# Pyr0-Piezo_Direct-Extruder-FFC-Breakout_.net
KiCad netlist of a schematic drawn in EAGLE
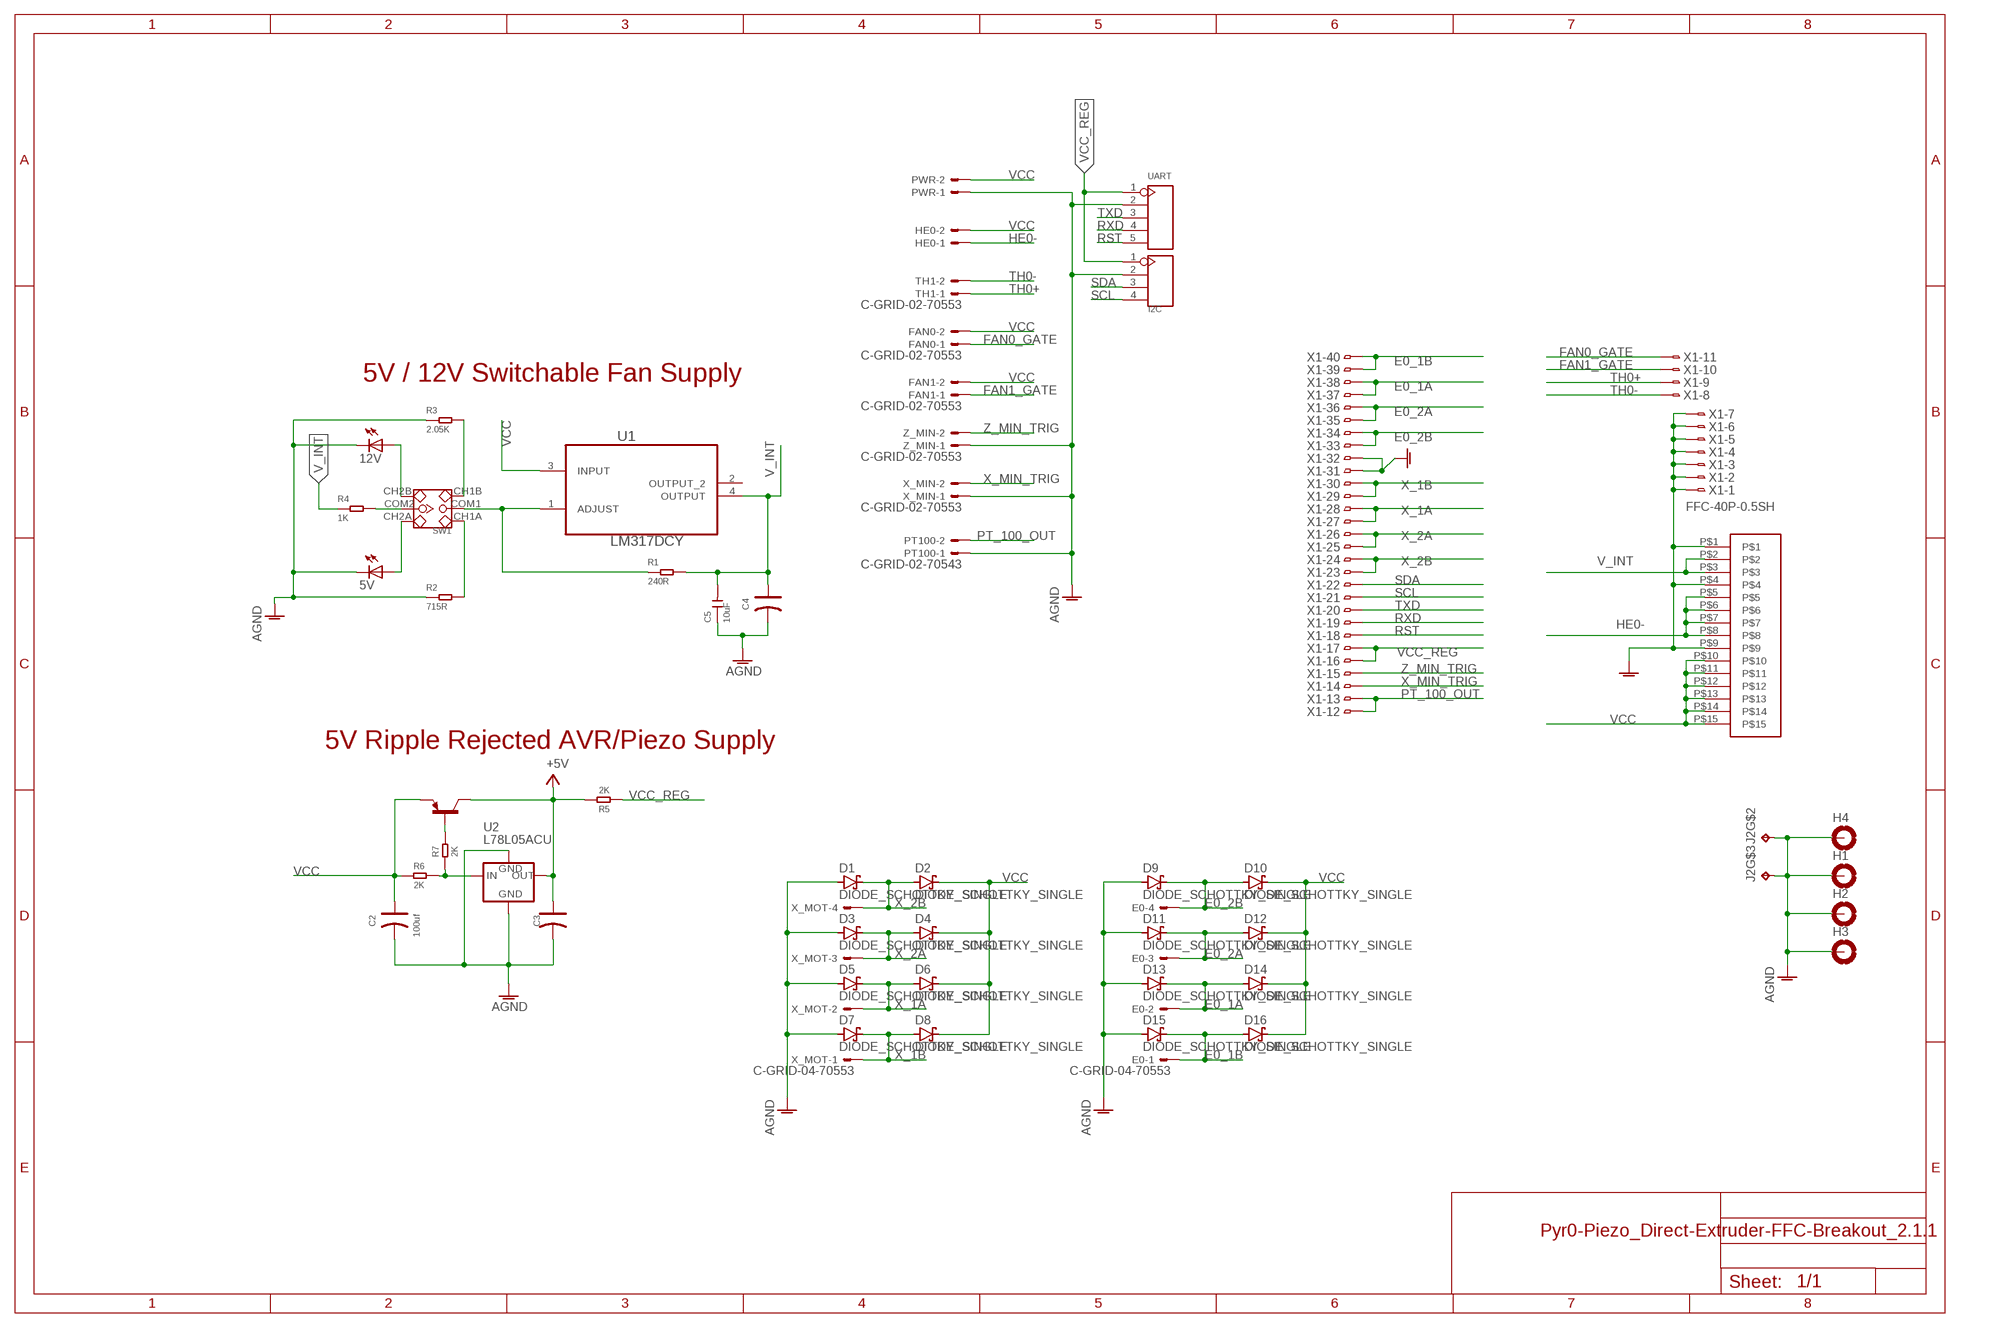
[diagram p0: schematic, sheet 1]

(export (version "E")
  (design (tool "Eeschema 10.0.6"))
  (components
    (comp (ref "5V")
      (value "LEDCHIP-LED0805")
      (footprint "eagle-import:CHIP-LED0805")
      (libsource (lib "eagle-import") (part "LEDCHIP-LED0805"))
    )
    (comp (ref "12V")
      (value "LEDCHIP-LED0805")
      (footprint "eagle-import:CHIP-LED0805")
      (libsource (lib "eagle-import") (part "LEDCHIP-LED0805"))
    )
    (comp (ref "C2")
      (value "100uf")
      (footprint "eagle-import:ALU-C-D5.3MM_LEFT")
      (fields (field (name "MPN") "KS 100uF/16V"))
      (libsource (lib "eagle-import") (part "DIP-ALUMINUM-100UF-16V(D5-H7MM)LEFT"))
    )
    (comp (ref "C3")
      (value "100uf")
      (footprint "eagle-import:ALU-C-D5.3MM_RIGHT")
      (libsource (lib "eagle-import") (part "DIP-ALUMINUM-100UF-16V(D5-H7MM)RIGHT"))
    )
    (comp (ref "C4")
      (value "100uf")
      (footprint "eagle-import:ALU-C-D5.3MM_RIGHT")
      (libsource (lib "eagle-import") (part "DIP-ALUMINUM-100UF-16V(D5-H7MM)RIGHT"))
    )
    (comp (ref "C5")
      (value "10uF")
      (footprint "eagle-import:CAPC2012X130")
      (libsource (lib "eagle-import") (part "SEEED-CAPACITOR_CERAMIC-10UF-25V-10%-X5R(0805)CAP_0805-3D"))
    )
    (comp (ref "D1")
      (value "DIODE_SCHOTTKY_SINGLE")
      (footprint "eagle-import:DO-214AC")
      (libsource (lib "eagle-import") (part "DIODE_SCHOTTKY_SINGLE"))
    )
    (comp (ref "D2")
      (value "DIODE_SCHOTTKY_SINGLE")
      (footprint "eagle-import:DO-214AC")
      (libsource (lib "eagle-import") (part "DIODE_SCHOTTKY_SINGLE"))
    )
    (comp (ref "D3")
      (value "DIODE_SCHOTTKY_SINGLE")
      (footprint "eagle-import:DO-214AC")
      (libsource (lib "eagle-import") (part "DIODE_SCHOTTKY_SINGLE"))
    )
    (comp (ref "D4")
      (value "DIODE_SCHOTTKY_SINGLE")
      (footprint "eagle-import:DO-214AC")
      (libsource (lib "eagle-import") (part "DIODE_SCHOTTKY_SINGLE"))
    )
    (comp (ref "D5")
      (value "DIODE_SCHOTTKY_SINGLE")
      (footprint "eagle-import:DO-214AC")
      (libsource (lib "eagle-import") (part "DIODE_SCHOTTKY_SINGLE"))
    )
    (comp (ref "D6")
      (value "DIODE_SCHOTTKY_SINGLE")
      (footprint "eagle-import:DO-214AC")
      (libsource (lib "eagle-import") (part "DIODE_SCHOTTKY_SINGLE"))
    )
    (comp (ref "D7")
      (value "DIODE_SCHOTTKY_SINGLE")
      (footprint "eagle-import:DO-214AC")
      (libsource (lib "eagle-import") (part "DIODE_SCHOTTKY_SINGLE"))
    )
    (comp (ref "D8")
      (value "DIODE_SCHOTTKY_SINGLE")
      (footprint "eagle-import:DO-214AC")
      (libsource (lib "eagle-import") (part "DIODE_SCHOTTKY_SINGLE"))
    )
    (comp (ref "D9")
      (value "DIODE_SCHOTTKY_SINGLE")
      (footprint "eagle-import:DO-214AC")
      (libsource (lib "eagle-import") (part "DIODE_SCHOTTKY_SINGLE"))
    )
    (comp (ref "D10")
      (value "DIODE_SCHOTTKY_SINGLE")
      (footprint "eagle-import:DO-214AC")
      (libsource (lib "eagle-import") (part "DIODE_SCHOTTKY_SINGLE"))
    )
    (comp (ref "D11")
      (value "DIODE_SCHOTTKY_SINGLE")
      (footprint "eagle-import:DO-214AC")
      (libsource (lib "eagle-import") (part "DIODE_SCHOTTKY_SINGLE"))
    )
    (comp (ref "D12")
      (value "DIODE_SCHOTTKY_SINGLE")
      (footprint "eagle-import:DO-214AC")
      (libsource (lib "eagle-import") (part "DIODE_SCHOTTKY_SINGLE"))
    )
    (comp (ref "D13")
      (value "DIODE_SCHOTTKY_SINGLE")
      (footprint "eagle-import:DO-214AC")
      (libsource (lib "eagle-import") (part "DIODE_SCHOTTKY_SINGLE"))
    )
    (comp (ref "D14")
      (value "DIODE_SCHOTTKY_SINGLE")
      (footprint "eagle-import:DO-214AC")
      (libsource (lib "eagle-import") (part "DIODE_SCHOTTKY_SINGLE"))
    )
    (comp (ref "D15")
      (value "DIODE_SCHOTTKY_SINGLE")
      (footprint "eagle-import:DO-214AC")
      (libsource (lib "eagle-import") (part "DIODE_SCHOTTKY_SINGLE"))
    )
    (comp (ref "D16")
      (value "DIODE_SCHOTTKY_SINGLE")
      (footprint "eagle-import:DO-214AC")
      (libsource (lib "eagle-import") (part "DIODE_SCHOTTKY_SINGLE"))
    )
    (comp (ref "E0")
      (value "C-GRID-04-70553")
      (footprint "eagle-import:70553-04")
      (fields (field (name "MF") "MOLEX"))
      (libsource (lib "eagle-import") (part "C-GRID-04-70553"))
    )
    (comp (ref "FAN0")
      (value "C-GRID-02-70553")
      (footprint "eagle-import:70553-02")
      (fields (field (name "MF") "MOLEX"))
      (libsource (lib "eagle-import") (part "C-GRID-02-70553"))
    )
    (comp (ref "FAN1")
      (value "C-GRID-02-70553")
      (footprint "eagle-import:70553-02")
      (fields (field (name "MF") "MOLEX"))
      (libsource (lib "eagle-import") (part "C-GRID-02-70553"))
    )
    (comp (ref "H1")
      (value "HOLES_MOUNT-PAD-ROUND3.2")
      (footprint "eagle-import:HOLES_3,2-PAD")
      (libsource (lib "eagle-import") (part "HOLES_MOUNT-PAD-ROUND3.2"))
    )
    (comp (ref "H2")
      (value "HOLES_MOUNT-PAD-ROUND3.2")
      (footprint "eagle-import:HOLES_3,2-PAD")
      (libsource (lib "eagle-import") (part "HOLES_MOUNT-PAD-ROUND3.2"))
    )
    (comp (ref "H3")
      (value "HOLES_MOUNT-PAD-ROUND3.2")
      (footprint "eagle-import:HOLES_3,2-PAD")
      (libsource (lib "eagle-import") (part "HOLES_MOUNT-PAD-ROUND3.2"))
    )
    (comp (ref "H4")
      (value "HOLES_MOUNT-PAD-ROUND3.2")
      (footprint "eagle-import:HOLES_3,2-PAD")
      (libsource (lib "eagle-import") (part "HOLES_MOUNT-PAD-ROUND3.2"))
    )
    (comp (ref "HE0")
      (value "KK-156-2")
      (footprint "eagle-import:KK-156-2")
      (fields (field (name "MF") "MOLEX"))
      (libsource (lib "eagle-import") (part "KK-156-2"))
    )
    (comp (ref "I2C")
      (value "SEEED-CONNECTOR_DIP-BLACK-FEMALE-HEADER-VERT(4P-2.54)JST-2.54MM_4P")
      (footprint "eagle-import:HDRVR4W64P254_1X4_1016X254X575B")
      (libsource (lib "eagle-import") (part "SEEED-CONNECTOR_DIP-BLACK-FEMALE-HEADER-VERT(4P-2.54)JST-2.54MM_4P"))
    )
    (comp (ref "J2")
      (value "FFC-15P-1MM")
      (footprint "eagle-import:FFC-15P-1MM")
      (libsource (lib "eagle-import") (part "FFC-15P-1MM"))
    )
    (comp (ref "PT100")
      (value "C-GRID-02-70543")
      (footprint "eagle-import:70543-02")
      (fields (field (name "MF") "MOLEX"))
      (libsource (lib "eagle-import") (part "C-GRID-02-70543"))
    )
    (comp (ref "PWR")
      (value "KK-156-2")
      (footprint "eagle-import:KK-156-2")
      (fields (field (name "MF") "MOLEX"))
      (libsource (lib "eagle-import") (part "KK-156-2"))
    )
    (comp (ref "Q2")
      (value "MMBT2907ALT1-PNP-SOT23-BEC")
      (footprint "eagle-import:SOT23-BEC")
      (libsource (lib "eagle-import") (part "-PNP-SOT23-BECMMBT2907ALT1"))
    )
    (comp (ref "R1")
      (value "240R")
      (footprint "eagle-import:SEEED-RESISTOR_R0603")
      (libsource (lib "eagle-import") (part "SEEED-RESISTOR_SMD-RES-1.5K-1%-1/10W(0603)DETAILED_MODEL"))
    )
    (comp (ref "R2")
      (value "715R")
      (footprint "eagle-import:SEEED-RESISTOR_R0603")
      (libsource (lib "eagle-import") (part "SEEED-RESISTOR_SMD-RES-1.5K-1%-1/10W(0603)DETAILED_MODEL"))
    )
    (comp (ref "R3")
      (value "2.05K")
      (footprint "eagle-import:SEEED-RESISTOR_R0603")
      (libsource (lib "eagle-import") (part "SEEED-RESISTOR_SMD-RES-1.5K-1%-1/10W(0603)DETAILED_MODEL"))
    )
    (comp (ref "R4")
      (value "1K")
      (footprint "eagle-import:SEEED-RESISTOR_R0603")
      (libsource (lib "eagle-import") (part "SEEED-RESISTOR_SMD-RES-1.5K-1%-1/10W(0603)DETAILED_MODEL"))
    )
    (comp (ref "R5")
      (value "2K")
      (footprint "eagle-import:R0805")
      (fields (field (name "MPN") "RC0805JR-072KL"))
      (libsource (lib "eagle-import") (part "SMD-RES-2K-5%-1/8W(0805)"))
    )
    (comp (ref "R6")
      (value "2K")
      (footprint "eagle-import:R0805")
      (fields (field (name "MPN") "RC0805JR-072KL"))
      (libsource (lib "eagle-import") (part "SMD-RES-2K-5%-1/8W(0805)"))
    )
    (comp (ref "R7")
      (value "2K")
      (footprint "eagle-import:R0805")
      (fields (field (name "MPN") "RC0805JR-072KL"))
      (libsource (lib "eagle-import") (part "SMD-RES-2K-5%-1/8W(0805)"))
    )
    (comp (ref "SW1")
      (value "SEEED-SWITCH_DIP-TOGGLE-SWITCH-2CH-(2X3P-2.54)DPDT_254_6P_UPDATE")
      (footprint "eagle-import:SEEED-SWITCH_SW6-2.54-9.0X3.5X3.2+2.0MM")
      (libsource (lib "eagle-import") (part "SEEED-SWITCH_DIP-TOGGLE-SWITCH-2CH-(2X3P-2.54)DPDT_254_6P_UPDATE"))
    )
    (comp (ref "TH1")
      (value "C-GRID-02-70553")
      (footprint "eagle-import:70553-02")
      (fields (field (name "MF") "MOLEX"))
      (libsource (lib "eagle-import") (part "C-GRID-02-70553"))
    )
    (comp (ref "U1")
      (value "LM317DCY")
      (footprint "eagle-import:SOT230P700X180-4N")
      (fields (field (name "MF") "Texas Instruments"))
      (libsource (lib "eagle-import") (part "LM317DCY"))
    )
    (comp (ref "U2")
      (value "L78L05ACU")
      (footprint "eagle-import:SOT89")
      (fields (field (name "MF") "STMicroelectronics") (field (name "MP") "L78L05ACU-TR"))
      (libsource (lib "eagle-import") (part "L78L05ACU"))
    )
    (comp (ref "UART")
      (value "JST-2.54MM_5P-2.54JST_2.54MM_5P_F")
      (footprint "eagle-import:HDRVR5W64P254_1X5_1270X254X575B")
      (libsource (lib "eagle-import") (part "JST-2.54MM_5P-2.54JST_2.54MM_5P_F"))
    )
    (comp (ref "X1")
      (value "FFC-40P-0.5SH")
      (footprint "eagle-import:FH12-40S-0.5SH")
      (fields (field (name "MPN") "FH12-40S-0.5SH(55)"))
      (libsource (lib "eagle-import") (part "FFC-40P-0.5SH"))
    )
    (comp (ref "X_MIN")
      (value "C-GRID-02-70553")
      (footprint "eagle-import:70553-02")
      (fields (field (name "MF") "MOLEX"))
      (libsource (lib "eagle-import") (part "C-GRID-02-70553"))
    )
    (comp (ref "X_MOT")
      (value "C-GRID-04-70553")
      (footprint "eagle-import:70553-04")
      (fields (field (name "MF") "MOLEX"))
      (libsource (lib "eagle-import") (part "C-GRID-04-70553"))
    )
    (comp (ref "Z_MIN")
      (value "C-GRID-02-70553")
      (footprint "eagle-import:70553-02")
      (fields (field (name "MF") "MOLEX"))
      (libsource (lib "eagle-import") (part "C-GRID-02-70553"))
    )
  )
  (nets
    (net (code "1") (name "+5V") (class "Default")
      (node (ref "C3") (pin "+") (pinfunction "+_+") (pintype "passive"))
      (node (ref "Q2") (pin "C") (pinfunction "C_C") (pintype "passive"))
      (node (ref "R5") (pin "2") (pinfunction "2_2") (pintype "passive"))
      (node (ref "U2") (pin "1") (pinfunction "OUT_1") (pintype "output"))
    )
    (net (code "2") (name "/E0_1A") (class "Default")
      (node (ref "D13") (pin "C") (pinfunction "C_C") (pintype "passive"))
      (node (ref "D14") (pin "A") (pinfunction "A_A") (pintype "passive"))
      (node (ref "E0") (pin "2") (pinfunction "S_2") (pintype "passive"))
      (node (ref "X1") (pin "37") (pinfunction "1_37") (pintype "passive"))
      (node (ref "X1") (pin "38") (pinfunction "1_38") (pintype "passive"))
    )
    (net (code "3") (name "/E0_1B") (class "Default")
      (node (ref "D15") (pin "C") (pinfunction "C_C") (pintype "passive"))
      (node (ref "D16") (pin "A") (pinfunction "A_A") (pintype "passive"))
      (node (ref "E0") (pin "1") (pinfunction "S_1") (pintype "passive"))
      (node (ref "X1") (pin "39") (pinfunction "1_39") (pintype "passive"))
      (node (ref "X1") (pin "40") (pinfunction "1_40") (pintype "passive"))
    )
    (net (code "4") (name "/E0_2A") (class "Default")
      (node (ref "D11") (pin "C") (pinfunction "C_C") (pintype "passive"))
      (node (ref "D12") (pin "A") (pinfunction "A_A") (pintype "passive"))
      (node (ref "E0") (pin "3") (pinfunction "S_3") (pintype "passive"))
      (node (ref "X1") (pin "35") (pinfunction "1_35") (pintype "passive"))
      (node (ref "X1") (pin "36") (pinfunction "1_36") (pintype "passive"))
    )
    (net (code "5") (name "/E0_2B") (class "Default")
      (node (ref "D10") (pin "A") (pinfunction "A_A") (pintype "passive"))
      (node (ref "D9") (pin "C") (pinfunction "C_C") (pintype "passive"))
      (node (ref "E0") (pin "4") (pinfunction "S_4") (pintype "passive"))
      (node (ref "X1") (pin "33") (pinfunction "1_33") (pintype "passive"))
      (node (ref "X1") (pin "34") (pinfunction "1_34") (pintype "passive"))
    )
    (net (code "6") (name "/FAN0_GATE") (class "Default")
      (node (ref "FAN0") (pin "1") (pinfunction "S_1") (pintype "passive"))
      (node (ref "X1") (pin "11") (pinfunction "1_11") (pintype "passive"))
    )
    (net (code "7") (name "/FAN1_GATE") (class "Default")
      (node (ref "FAN1") (pin "1") (pinfunction "S_1") (pintype "passive"))
      (node (ref "X1") (pin "10") (pinfunction "1_10") (pintype "passive"))
    )
    (net (code "8") (name "/HE0-") (class "Default")
      (node (ref "HE0") (pin "1") (pinfunction "S_1") (pintype "passive"))
      (node (ref "J2") (pin "P$5") (pinfunction "P$5_P$5") (pintype "bidirectional"))
      (node (ref "J2") (pin "P$6") (pinfunction "P$6_P$6") (pintype "bidirectional"))
      (node (ref "J2") (pin "P$7") (pinfunction "P$7_P$7") (pintype "bidirectional"))
      (node (ref "J2") (pin "P$8") (pinfunction "P$8_P$8") (pintype "bidirectional"))
    )
    (net (code "9") (name "/PT_100_OUT") (class "Default")
      (node (ref "PT100") (pin "2") (pinfunction "S_2") (pintype "passive"))
      (node (ref "X1") (pin "12") (pinfunction "1_12") (pintype "passive"))
      (node (ref "X1") (pin "13") (pinfunction "1_13") (pintype "passive"))
    )
    (net (code "10") (name "/RST") (class "Default")
      (node (ref "UART") (pin "5") (pinfunction "P$5_5") (pintype "bidirectional"))
      (node (ref "X1") (pin "18") (pinfunction "1_18") (pintype "passive"))
    )
    (net (code "11") (name "/RXD") (class "Default")
      (node (ref "UART") (pin "4") (pinfunction "P$4_4") (pintype "bidirectional"))
      (node (ref "X1") (pin "19") (pinfunction "1_19") (pintype "passive"))
    )
    (net (code "12") (name "/SCL") (class "Default")
      (node (ref "I2C") (pin "4") (pinfunction "P$4_4") (pintype "bidirectional"))
      (node (ref "X1") (pin "21") (pinfunction "1_21") (pintype "passive"))
    )
    (net (code "13") (name "/SDA") (class "Default")
      (node (ref "I2C") (pin "3") (pinfunction "P$3_3") (pintype "bidirectional"))
      (node (ref "X1") (pin "22") (pinfunction "1_22") (pintype "passive"))
    )
    (net (code "14") (name "/TH0+") (class "Default")
      (node (ref "TH1") (pin "1") (pinfunction "S_1") (pintype "passive"))
      (node (ref "X1") (pin "9") (pinfunction "1_9") (pintype "passive"))
    )
    (net (code "15") (name "/TH0-") (class "Default")
      (node (ref "TH1") (pin "2") (pinfunction "S_2") (pintype "passive"))
      (node (ref "X1") (pin "8") (pinfunction "1_8") (pintype "passive"))
    )
    (net (code "16") (name "/TXD") (class "Default")
      (node (ref "UART") (pin "3") (pinfunction "P$3_3") (pintype "bidirectional"))
      (node (ref "X1") (pin "20") (pinfunction "1_20") (pintype "passive"))
    )
    (net (code "17") (name "/VCC") (class "Default")
      (node (ref "C2") (pin "+") (pinfunction "+_+") (pintype "passive"))
      (node (ref "D10") (pin "C") (pinfunction "C_C") (pintype "passive"))
      (node (ref "D12") (pin "C") (pinfunction "C_C") (pintype "passive"))
      (node (ref "D14") (pin "C") (pinfunction "C_C") (pintype "passive"))
      (node (ref "D16") (pin "C") (pinfunction "C_C") (pintype "passive"))
      (node (ref "D2") (pin "C") (pinfunction "C_C") (pintype "passive"))
      (node (ref "D4") (pin "C") (pinfunction "C_C") (pintype "passive"))
      (node (ref "D6") (pin "C") (pinfunction "C_C") (pintype "passive"))
      (node (ref "D8") (pin "C") (pinfunction "C_C") (pintype "passive"))
      (node (ref "FAN0") (pin "2") (pinfunction "S_2") (pintype "passive"))
      (node (ref "FAN1") (pin "2") (pinfunction "S_2") (pintype "passive"))
      (node (ref "HE0") (pin "2") (pinfunction "S_2") (pintype "passive"))
      (node (ref "J2") (pin "P$10") (pinfunction "P$10_P$10") (pintype "bidirectional"))
      (node (ref "J2") (pin "P$11") (pinfunction "P$11_P$11") (pintype "bidirectional"))
      (node (ref "J2") (pin "P$12") (pinfunction "P$12_P$12") (pintype "bidirectional"))
      (node (ref "J2") (pin "P$13") (pinfunction "P$13_P$13") (pintype "bidirectional"))
      (node (ref "J2") (pin "P$14") (pinfunction "P$14_P$14") (pintype "bidirectional"))
      (node (ref "J2") (pin "P$15") (pinfunction "P$15_P$15") (pintype "bidirectional"))
      (node (ref "PWR") (pin "2") (pinfunction "S_2") (pintype "passive"))
      (node (ref "Q2") (pin "E") (pinfunction "E_E") (pintype "passive"))
      (node (ref "R6") (pin "1") (pinfunction "1_1") (pintype "passive"))
      (node (ref "U1") (pin "3") (pinfunction "INPUT_3") (pintype "input"))
    )
    (net (code "18") (name "/X_1A") (class "Default")
      (node (ref "D5") (pin "C") (pinfunction "C_C") (pintype "passive"))
      (node (ref "D6") (pin "A") (pinfunction "A_A") (pintype "passive"))
      (node (ref "X1") (pin "27") (pinfunction "1_27") (pintype "passive"))
      (node (ref "X1") (pin "28") (pinfunction "1_28") (pintype "passive"))
      (node (ref "X_MOT") (pin "2") (pinfunction "S_2") (pintype "passive"))
    )
    (net (code "19") (name "/X_1B") (class "Default")
      (node (ref "D7") (pin "C") (pinfunction "C_C") (pintype "passive"))
      (node (ref "D8") (pin "A") (pinfunction "A_A") (pintype "passive"))
      (node (ref "X1") (pin "29") (pinfunction "1_29") (pintype "passive"))
      (node (ref "X1") (pin "30") (pinfunction "1_30") (pintype "passive"))
      (node (ref "X_MOT") (pin "1") (pinfunction "S_1") (pintype "passive"))
    )
    (net (code "20") (name "/X_2A") (class "Default")
      (node (ref "D3") (pin "C") (pinfunction "C_C") (pintype "passive"))
      (node (ref "D4") (pin "A") (pinfunction "A_A") (pintype "passive"))
      (node (ref "X1") (pin "25") (pinfunction "1_25") (pintype "passive"))
      (node (ref "X1") (pin "26") (pinfunction "1_26") (pintype "passive"))
      (node (ref "X_MOT") (pin "3") (pinfunction "S_3") (pintype "passive"))
    )
    (net (code "21") (name "/X_2B") (class "Default")
      (node (ref "D1") (pin "C") (pinfunction "C_C") (pintype "passive"))
      (node (ref "D2") (pin "A") (pinfunction "A_A") (pintype "passive"))
      (node (ref "X1") (pin "23") (pinfunction "1_23") (pintype "passive"))
      (node (ref "X1") (pin "24") (pinfunction "1_24") (pintype "passive"))
      (node (ref "X_MOT") (pin "4") (pinfunction "S_4") (pintype "passive"))
    )
    (net (code "22") (name "/X_MIN_TRIG") (class "Default")
      (node (ref "X1") (pin "14") (pinfunction "1_14") (pintype "passive"))
      (node (ref "X_MIN") (pin "2") (pinfunction "S_2") (pintype "passive"))
    )
    (net (code "23") (name "/Z_MIN_TRIG") (class "Default")
      (node (ref "X1") (pin "15") (pinfunction "1_15") (pintype "passive"))
      (node (ref "Z_MIN") (pin "2") (pinfunction "S_2") (pintype "passive"))
    )
    (net (code "24") (name "AGND") (class "Default")
      (node (ref "12V") (pin "C") (pinfunction "C_C") (pintype "passive"))
      (node (ref "5V") (pin "C") (pinfunction "C_C") (pintype "passive"))
      (node (ref "C2") (pin "-") (pinfunction "-_-") (pintype "passive"))
      (node (ref "C3") (pin "-") (pinfunction "-_-") (pintype "passive"))
      (node (ref "C4") (pin "-") (pinfunction "-_-") (pintype "passive"))
      (node (ref "C5") (pin "1") (pinfunction "1_1") (pintype "passive"))
      (node (ref "D1") (pin "A") (pinfunction "A_A") (pintype "passive"))
      (node (ref "D11") (pin "A") (pinfunction "A_A") (pintype "passive"))
      (node (ref "D13") (pin "A") (pinfunction "A_A") (pintype "passive"))
      (node (ref "D15") (pin "A") (pinfunction "A_A") (pintype "passive"))
      (node (ref "D3") (pin "A") (pinfunction "A_A") (pintype "passive"))
      (node (ref "D5") (pin "A") (pinfunction "A_A") (pintype "passive"))
      (node (ref "D7") (pin "A") (pinfunction "A_A") (pintype "passive"))
      (node (ref "D9") (pin "A") (pinfunction "A_A") (pintype "passive"))
      (node (ref "H1") (pin "B3,2") (pinfunction "MOUNT_B3,2") (pintype "passive"))
      (node (ref "H2") (pin "B3,2") (pinfunction "MOUNT_B3,2") (pintype "passive"))
      (node (ref "H3") (pin "B3,2") (pinfunction "MOUNT_B3,2") (pintype "passive"))
      (node (ref "H4") (pin "B3,2") (pinfunction "MOUNT_B3,2") (pintype "passive"))
      (node (ref "I2C") (pin "2") (pinfunction "P$2_2") (pintype "bidirectional"))
      (node (ref "J2") (pin "P$1") (pinfunction "P$1_P$1") (pintype "bidirectional"))
      (node (ref "J2") (pin "P$16") (pinfunction "TP_P$16") (pintype "input"))
      (node (ref "J2") (pin "P$17") (pinfunction "TP_P$17") (pintype "input"))
      (node (ref "J2") (pin "P$4") (pinfunction "P$4_P$4") (pintype "bidirectional"))
      (node (ref "J2") (pin "P$9") (pinfunction "P$9_P$9") (pintype "bidirectional"))
      (node (ref "PT100") (pin "1") (pinfunction "S_1") (pintype "passive"))
      (node (ref "PWR") (pin "1") (pinfunction "S_1") (pintype "passive"))
      (node (ref "R2") (pin "1") (pinfunction "1_1") (pintype "passive"))
      (node (ref "R3") (pin "1") (pinfunction "1_1") (pintype "passive"))
      (node (ref "U2") (pin "2") (pinfunction "GND_2") (pintype "power_in"))
      (node (ref "U2") (pin "PAD") (pinfunction "PAD_PAD") (pintype "power_in"))
      (node (ref "UART") (pin "2") (pinfunction "P$2_2") (pintype "bidirectional"))
      (node (ref "X1") (pin "1") (pinfunction "1_1") (pintype "passive"))
      (node (ref "X1") (pin "2") (pinfunction "1_2") (pintype "passive"))
      (node (ref "X1") (pin "3") (pinfunction "1_3") (pintype "passive"))
      (node (ref "X1") (pin "31") (pinfunction "1_31") (pintype "passive"))
      (node (ref "X1") (pin "32") (pinfunction "1_32") (pintype "passive"))
      (node (ref "X1") (pin "4") (pinfunction "1_4") (pintype "passive"))
      (node (ref "X1") (pin "5") (pinfunction "1_5") (pintype "passive"))
      (node (ref "X1") (pin "6") (pinfunction "1_6") (pintype "passive"))
      (node (ref "X1") (pin "7") (pinfunction "1_7") (pintype "passive"))
      (node (ref "X_MIN") (pin "1") (pinfunction "S_1") (pintype "passive"))
      (node (ref "Z_MIN") (pin "1") (pinfunction "S_1") (pintype "passive"))
    )
    (net (code "25") (name "Net-(5V-PadA)") (class "Default")
      (node (ref "5V") (pin "A") (pinfunction "A_A") (pintype "passive"))
      (node (ref "SW1") (pin "CH2A") (pinfunction "CH2A_CH2A") (pintype "bidirectional"))
    )
    (net (code "26") (name "Net-(12V-PadA)") (class "Default")
      (node (ref "12V") (pin "A") (pinfunction "A_A") (pintype "passive"))
      (node (ref "SW1") (pin "CH2B") (pinfunction "CH2B_CH2B") (pintype "bidirectional"))
    )
    (net (code "27") (name "Net-(Q2-PadB)") (class "Default")
      (node (ref "Q2") (pin "B") (pinfunction "B_B") (pintype "passive"))
      (node (ref "R7") (pin "2") (pinfunction "2_2") (pintype "passive"))
    )
    (net (code "28") (name "Net-(R2-Pad2)") (class "Default")
      (node (ref "R2") (pin "2") (pinfunction "2_2") (pintype "passive"))
      (node (ref "SW1") (pin "CH1A") (pinfunction "CH1A_CH1A") (pintype "bidirectional"))
    )
    (net (code "29") (name "Net-(R3-Pad2)") (class "Default")
      (node (ref "R3") (pin "2") (pinfunction "2_2") (pintype "passive"))
      (node (ref "SW1") (pin "CH1B") (pinfunction "CH1B_CH1B") (pintype "bidirectional"))
    )
    (net (code "30") (name "Net-(R4-Pad2)") (class "Default")
      (node (ref "R4") (pin "2") (pinfunction "2_2") (pintype "passive"))
      (node (ref "SW1") (pin "COM2") (pinfunction "COM2_COM2") (pintype "bidirectional"))
    )
    (net (code "31") (name "Net-(U1-ADJUST)") (class "Default")
      (node (ref "R1") (pin "1") (pinfunction "1_1") (pintype "passive"))
      (node (ref "SW1") (pin "COM1") (pinfunction "COM1_COM1") (pintype "bidirectional"))
      (node (ref "U1") (pin "1") (pinfunction "ADJUST_1") (pintype "input"))
    )
    (net (code "32") (name "Net-(U2-IN)") (class "Default")
      (node (ref "R6") (pin "2") (pinfunction "2_2") (pintype "passive"))
      (node (ref "R7") (pin "1") (pinfunction "1_1") (pintype "passive"))
      (node (ref "U2") (pin "3") (pinfunction "IN_3") (pintype "input"))
    )
    (net (code "33") (name "VCC_REG") (class "Default")
      (node (ref "I2C") (pin "1") (pinfunction "P$1_1") (pintype "bidirectional"))
      (node (ref "R5") (pin "1") (pinfunction "1_1") (pintype "passive"))
      (node (ref "UART") (pin "1") (pinfunction "P$1_1") (pintype "bidirectional"))
      (node (ref "X1") (pin "16") (pinfunction "1_16") (pintype "passive"))
      (node (ref "X1") (pin "17") (pinfunction "1_17") (pintype "passive"))
    )
    (net (code "34") (name "V_INT") (class "Default")
      (node (ref "C4") (pin "+") (pinfunction "+_+") (pintype "passive"))
      (node (ref "C5") (pin "2") (pinfunction "2_2") (pintype "passive"))
      (node (ref "J2") (pin "P$2") (pinfunction "P$2_P$2") (pintype "bidirectional"))
      (node (ref "J2") (pin "P$3") (pinfunction "P$3_P$3") (pintype "bidirectional"))
      (node (ref "R1") (pin "2") (pinfunction "2_2") (pintype "passive"))
      (node (ref "R4") (pin "1") (pinfunction "1_1") (pintype "passive"))
      (node (ref "U1") (pin "4") (pinfunction "OUTPUT_4") (pintype "output"))
    )
    (net (code "35") (name "unconnected-(U1-OUTPUT_2-Pad2)") (class "Default")
      (node (ref "U1") (pin "2") (pinfunction "OUTPUT_2_2") (pintype "output"))
    )
  )
)
